# 12V-2A-buck.net
KiCad netlist of a schematic drawn in Altium Designer
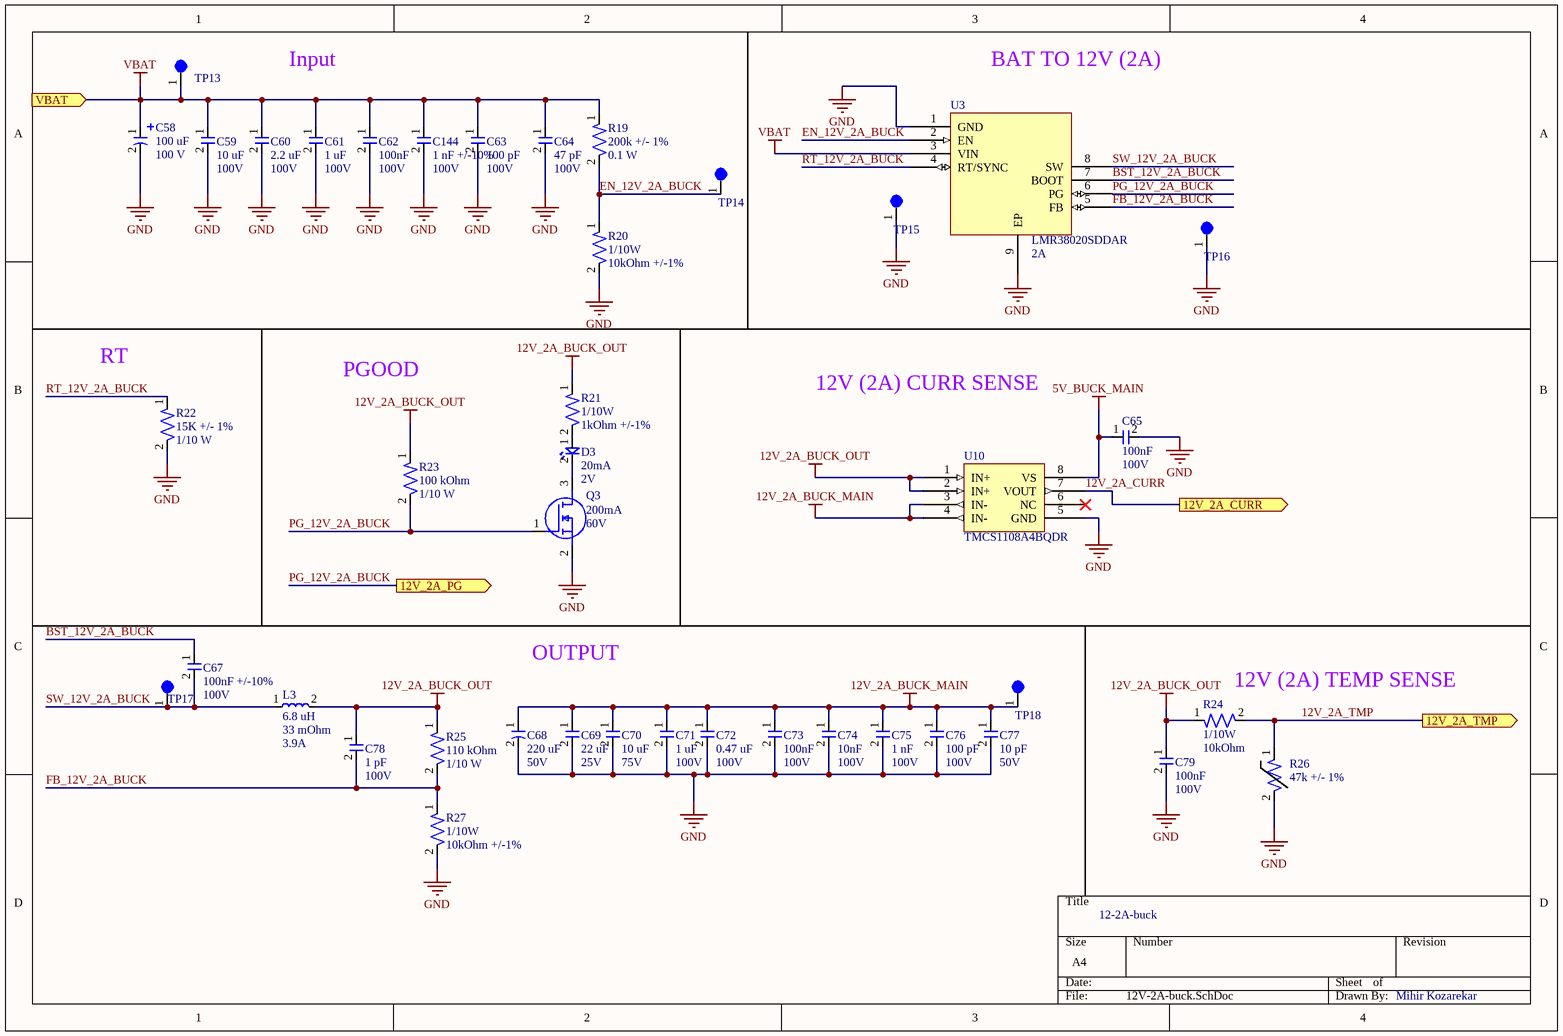
[diagram p0: 12V-2A-buck.SchDoc]

(export (version "E")
  (design (tool "Eeschema 10.0.6"))
  (components
    (comp (ref "C58")
      (value "100SEV100M12.5X16")
      (footprint "ELEC-100U-0001")
      (description "100 µF 100 V Aluminum Electrolytic Capacitors Radial, Can - SMD 2000 Hrs @ 85°C")
      (fields
        (field (name "MANUFACTURER") "Rubycon")
        (field (name "TOLERANCE") "+/- 20%")
        (field (name "CAPACITANCE") "100 uF")
        (field (name "VOLTAGE") "100 V")
      )
      (libsource (lib "MasterLib") (part "ELEC-100U-0001"))
    )
    (comp (ref "C59")
      (value "GRM32EC72A106KE05L")
      (footprint "CAP-1210")
      (description "10 µF ±10% 100V Ceramic Capacitor X7S 1210 (3225 Metric)")
      (fields (field (name "CAPCITANCE") "10 uF") (field (name "VOLTAGE RATING") "100V"))
      (libsource (lib "MasterLib") (part "CAP-10U-0003"))
    )
    (comp (ref "C60")
      (value "CL31B225KCHSNNE")
      (footprint "CAP-1206")
      (description "2.2 µF ±10% 100V Ceramic Capacitor X7R 1206 (3216 Metric)")
      (fields
        (field (name "MANUFACTURER") "Samsung Electro-Mechanics")
        (field (name "TOLERANCE") "+/- 10%")
        (field (name "CAPACITANCE") "2.2 uF")
        (field (name "VOLTAGE") "100V")
      )
      (libsource (lib "MasterLib") (part "CAP-2.2U-0003"))
    )
    (comp (ref "C61")
      (value "CL31B105KCHNNNE")
      (footprint "CAP-1206 - duplicate")
      (description "1 µF ±10% 100V Ceramic Capacitor X7R 1206 (3216 Metric)")
      (fields (field (name "CAPACITANCE") "1 uF") (field (name "VOLTAGE") "100V"))
      (libsource (lib "MasterLib") (part "CAP-1U-0001"))
    )
    (comp (ref "C62")
      (value "CC0603KRX7R0BB104")
      (footprint "CAP-0603")
      (description "CAP CER 0.1UF 100V X7R 0603")
      (fields
        (field (name "MANUFACTURER") "YAGEO")
        (field (name "CAPACITANCE") "100nF")
        (field (name "VOLTAGE RATING") "100V")
      )
      (libsource (lib "MasterLib") (part "CAP-100N-0001"))
    )
    (comp (ref "C63")
      (value "0603N101J101CT")
      (footprint "CAP-0603")
      (description "100 pF ±5% 100V Ceramic Capacitor C0G, NP0 0603 (1608 Metric)")
      (fields
        (field (name "TOLERANCE") "+/-5%")
        (field (name "CAPACITANCE") "100 pF")
        (field (name "VOLTAGE") "100V")
      )
      (libsource (lib "MasterLib") (part "CAP-100P-0002"))
    )
    (comp (ref "C64")
      (value "7447798111")
      (footprint "CAP-0603")
      (description "47 pF ±5% 100V Ceramic Capacitor C0G, NP0 0603 (1608 Metric)")
      (fields (field (name "CAPACITANCE") "47 pF") (field (name "VOLTAGE RATING") "100V"))
      (libsource (lib "MasterLib") (part "CAP-47P-0001"))
    )
    (comp (ref "C65")
      (value "CC0603KRX7R0BB104")
      (footprint "CAP-0603")
      (description "CAP CER 0.1UF 100V X7R 0603")
      (fields
        (field (name "MANUFACTURER") "YAGEO")
        (field (name "CAPACITANCE") "100nF")
        (field (name "VOLTAGE RATING") "100V")
      )
      (libsource (lib "MasterLib") (part "CAP-100N-0001"))
    )
    (comp (ref "C67")
      (value "CC0603KRX7R0BB104")
      (footprint "CAP-0603")
      (description "CAP CER 0.1UF 100V X7R 0603")
      (fields
        (field (name "MANUFACTURER") "YAGEO")
        (field (name "CAPACITANCE") "100nF +/-10%")
        (field (name "VOLTAGE RATING") "100V")
      )
      (libsource (lib "MasterLib") (part "CAP-100N-0001"))
    )
    (comp (ref "C68")
      (value "50TZV220M10X10.5")
      (footprint "ELEC-220U-0003")
      (description "220 µF 50 V Aluminum Electrolytic Capacitors Radial, Can - SMD 2000 Hrs @ 105°C")
      (fields (field (name "CAPACITANCE") "220 uF") (field (name "VOLTAGE RATING") "50V"))
      (libsource (lib "MasterLib") (part "ELEC-220U-0003"))
    )
    (comp (ref "C69")
      (value "CL32B226KAJNNNE")
      (footprint "CAP-1210")
      (description "22 µF ±10% 25V Ceramic Capacitor X7R 1210 (3225 Metric)")
      (fields
        (field (name "TOLERANCE") "+/- 10%")
        (field (name "CAPACITANCE") "22 uF")
        (field (name "VOLTAGE") "25V")
      )
      (libsource (lib "MasterLib") (part "CAP-22U-0003"))
    )
    (comp (ref "C70")
      (value "C3225X7R1N106K250AC")
      (footprint "CAP-1210")
      (description "10 µF ±10% 75V Ceramic Capacitor X7R 1210 (3225 Metric)")
      (fields (field (name "CAPACITANCE") "10 uF") (field (name "VOLTAGE RATING") "75V"))
      (libsource (lib "MasterLib") (part "CAP-10U-0004"))
    )
    (comp (ref "C71")
      (value "CL31B105KCHNNNE")
      (footprint "CAP-1206 - duplicate")
      (description "1 µF ±10% 100V Ceramic Capacitor X7R 1206 (3216 Metric)")
      (fields (field (name "CAPACITANCE") "1 uF") (field (name "VOLTAGE") "100V"))
      (libsource (lib "MasterLib") (part "CAP-1U-0001"))
    )
    (comp (ref "C72")
      (value "KAM21KR72A474KL")
      (footprint "CAP-0805")
      (description "0.47 µF ±10% 100V Ceramic Capacitor X7R 0805 (2012 Metric)")
      (fields
        (field (name "TOLERANCE") "+/- 10%")
        (field (name "CAPACITANCE") "0.47 uF")
        (field (name "VOLTAGE") "100V")
      )
      (libsource (lib "MasterLib") (part "CAP-0.47U-0001"))
    )
    (comp (ref "C73")
      (value "CC0603KRX7R0BB104")
      (footprint "CAP-0603")
      (description "CAP CER 0.1UF 100V X7R 0603")
      (fields
        (field (name "MANUFACTURER") "YAGEO")
        (field (name "CAPACITANCE") "100nF")
        (field (name "VOLTAGE RATING") "100V")
      )
      (libsource (lib "MasterLib") (part "CAP-100N-0001"))
    )
    (comp (ref "C74")
      (value "C1608C0G2A103J080AC")
      (footprint "CAP-0603")
      (description "CAP CER 10000PF 100V C0G 0603")
      (fields
        (field (name "MANUFACTURER") "TDK Corporation")
        (field (name "CAPACITANCE") "10nF")
        (field (name "VOLTAGE RATING") "100V")
      )
      (libsource (lib "MasterLib") (part "CAP-10N-0002"))
    )
    (comp (ref "C75")
      (value "C0603Y102K1RAC7867")
      (footprint "CAP-0603")
      (description "1000 pF ±10% 100V Ceramic Capacitor X7R 0603 (1608 Metric)")
      (fields (field (name "CAPACITANCE") "1 nF") (field (name "VOLTAGE") "100V"))
      (libsource (lib "MasterLib") (part "CAP-1N-0001"))
    )
    (comp (ref "C76")
      (value "0603N101J101CT")
      (footprint "CAP-0603")
      (description "100 pF ±5% 100V Ceramic Capacitor C0G, NP0 0603 (1608 Metric)")
      (fields
        (field (name "TOLERANCE") "+/-5%")
        (field (name "CAPACITANCE") "100 pF")
        (field (name "VOLTAGE") "100V")
      )
      (libsource (lib "MasterLib") (part "CAP-100P-0002"))
    )
    (comp (ref "C77")
      (value "0603N100J500CT")
      (footprint "CAP-0603")
      (description "10 pF ±5% 50V Ceramic Capacitor C0G, NP0 0603 (1608 Metric)")
      (fields
        (field (name "MANUFACTURER") "Walshin Technology Corporation")
        (field (name "CAPACITANCE") "10 pF")
        (field (name "VOLTAGE RATING") "50V")
      )
      (libsource (lib "MasterLib") (part "CAP-10P-0001"))
    )
    (comp (ref "C78")
      (value "885012006087")
      (footprint "CAP-0603")
      (description "1 pF ±0.25pF 100V Ceramic Capacitor C0G, NP0 0603 (1608 Metric)")
      (fields
        (field (name "TOLERANCE") "+/- 0.25 pF")
        (field (name "CAPACITANCE") "1 pF")
        (field (name "VOLTAGE") "100V")
      )
      (libsource (lib "MasterLib") (part "CAP-1P-0001"))
    )
    (comp (ref "C79")
      (value "CC0603KRX7R0BB104")
      (footprint "CAP-0603")
      (description "CAP CER 0.1UF 100V X7R 0603")
      (fields
        (field (name "MANUFACTURER") "YAGEO")
        (field (name "CAPACITANCE") "100nF")
        (field (name "VOLTAGE RATING") "100V")
      )
      (libsource (lib "MasterLib") (part "CAP-100N-0001"))
    )
    (comp (ref "C144")
      (value "C0603Y102K1RAC7867")
      (footprint "CAP-0603")
      (description "1000 pF ±10% 100V Ceramic Capacitor X7R 0603 (1608 Metric)")
      (fields (field (name "CAPACITANCE") "1 nF +/-10%") (field (name "VOLTAGE") "100V"))
      (libsource (lib "MasterLib") (part "CAP-1N-0001"))
    )
    (comp (ref "D3")
      (value "150060AS75000")
      (footprint "LED-0603")
      (description "CAP CER 0.1UF 100V X7R 0603")
      (fields
        (field (name "MANUFACTURER") "Wurth Electronik")
        (field (name "CURRENT RATING") "20mA")
        (field (name "VF") "2V")
      )
      (libsource (lib "MasterLib") (part "LED_Amber_0001"))
    )
    (comp (ref "L3")
      (value "SRN8040-6R8Y")
      (footprint "PWRIND-6.8U-0001")
      (description "6.8 µH Semi-Shielded Drum Core, Wirewound Inductor 3.9 A 33mOhm Max Nonstandard")
      (fields
        (field (name "TOLERANCE") "30%")
        (field (name "INDUCTANCE") "6.8 uH")
        (field (name "DCR") "33 mOhm")
        (field (name "DCI") "3.9A")
      )
      (libsource (lib "MasterLib") (part "PWRIND-6.8U-0001"))
    )
    (comp (ref "Q3")
      (value "T2N7002AK,LM")
      (footprint "NMOS-SOT23-3")
      (description "MOSFET N-CH 60V 200MA SOT23")
      (fields
        (field (name "MANUFACTURER") "Toshiba")
        (field (name "ID-CONTINUOUS") "200mA")
        (field (name "VDS-MAX") "60V")
      )
      (libsource (lib "MasterLib") (part "NMOS-200MA-0001"))
    )
    (comp (ref "R19")
      (value "ERJ-3EKF2003V")
      (footprint "RES-0603")
      (description "200 kOhms ±1% 0.1W, 1/10W Chip Resistor 0603 (1608 Metric) Automotive AEC-Q200 Thick Film")
      (fields
        (field (name "MANUFACTURER") "Panasonic Electronic Components")
        (field (name "RESISTANCE") "200k +/- 1%")
        (field (name "POWER RATING") "0.1 W")
      )
      (libsource (lib "MasterLib") (part "RES-200K-0001"))
    )
    (comp (ref "R20")
      (value "RC0603FR-0710KP")
      (footprint "RES-0603")
      (description "RES SMD 10K OHM 1% 1/10W 0603")
      (fields
        (field (name "MANUFACTURER") "YAGEO")
        (field (name "POWER RATING") "1/10W")
        (field (name "RESISTANCE") "10kOhm +/-1%")
      )
      (libsource (lib "MasterLib") (part "RES-10K-0002"))
    )
    (comp (ref "R21")
      (value "RT0603FRE131KL")
      (footprint "RES-0603")
      (description "1 kOhms ±1% 0.1W, 1/10W Chip Resistor 0603 (1608 Metric) Thin Film")
      (fields
        (field (name "MANUFACTURER") "YAGEO")
        (field (name "POWER RATING") "1/10W")
        (field (name "RESISTANCE") "1kOhm +/-1%")
      )
      (libsource (lib "MasterLib") (part "RES-1K-0002"))
    )
    (comp (ref "R22")
      (value "ERJ-2RKF1502X")
      (footprint "RES-0402")
      (description "15 kOhms ±1% 0.1W, 1/10W Chip Resistor 0402 (1005 Metric) Automotive AEC-Q200 Thick Film")
      (fields (field (name "RES") "15K +/- 1%") (field (name "POWER") "1/10 W"))
      (libsource (lib "MasterLib") (part "RES-15K-0001"))
    )
    (comp (ref "R23")
      (value "RC0603FR-07100KL")
      (footprint "RES-0603")
      (description "100 kOhms ±1% 0.1W, 1/10W Chip Resistor 0603 (1608 Metric) Moisture Resistant Thick Film")
      (fields
        (field (name "TOLERANCE") "+/- 1%")
        (field (name "RESISTANCE") "100 kOhm")
        (field (name "POWER") "1/10 W")
      )
      (libsource (lib "MasterLib") (part "RES-100K-0003"))
    )
    (comp (ref "R24")
      (value "RC0603FR-0710KP")
      (footprint "RES-0603")
      (description "RES SMD 10K OHM 1% 1/10W 0603")
      (fields
        (field (name "MANUFACTURER") "YAGEO")
        (field (name "POWER RATING") "1/10W")
        (field (name "RESISTANCE") "10kOhm")
      )
      (libsource (lib "MasterLib") (part "RES-10K-0002"))
    )
    (comp (ref "R25")
      (value "RC0603FR-07110KL")
      (footprint "RES-0603")
      (description "110 kOhms ±1% 0.1W, 1/10W Chip Resistor 0603 (1608 Metric) Moisture Resistant Thick Film")
      (fields
        (field (name "TOLERANCE") "+/- 1%")
        (field (name "RESISTANCE") "110 kOhm")
        (field (name "POWER") "1/10 W")
      )
      (libsource (lib "MasterLib") (part "RES-110K-0001"))
    )
    (comp (ref "R26")
      (value "TMP6431DECR")
      (footprint "RES-0402")
      (description "PTC Thermistor 47 kOhms 0402 (1006 Metric)")
      (fields (field (name "MANUFACTURER") "Texas Instruments") (field (name "RESISTANCE") "47k +/- 1%"))
      (libsource (lib "MasterLib") (part "THERM-47K-0001"))
    )
    (comp (ref "R27")
      (value "RC0603FR-0710KP")
      (footprint "RES-0603")
      (description "RES SMD 10K OHM 1% 1/10W 0603")
      (fields
        (field (name "MANUFACTURER") "YAGEO")
        (field (name "POWER RATING") "1/10W")
        (field (name "RESISTANCE") "10kOhm +/-1%")
      )
      (libsource (lib "MasterLib") (part "RES-10K-0002"))
    )
    (comp (ref "TP13")
      (value "5003")
      (footprint "TEST-POINT-0001")
      (description "Oranange PC Test Point, Miniature Phoisphor Bronze Silver Plating Through Hole Mounting Type")
      (libsource (lib "MasterLib") (part "TEST-POINT-0001"))
    )
    (comp (ref "TP14")
      (value "5003")
      (footprint "TEST-POINT-0001")
      (description "Oranange PC Test Point, Miniature Phoisphor Bronze Silver Plating Through Hole Mounting Type")
      (libsource (lib "MasterLib") (part "TEST-POINT-0001"))
    )
    (comp (ref "TP15")
      (value "5003")
      (footprint "TEST-POINT-0001")
      (description "Oranange PC Test Point, Miniature Phoisphor Bronze Silver Plating Through Hole Mounting Type")
      (libsource (lib "MasterLib") (part "TEST-POINT-0001"))
    )
    (comp (ref "TP16")
      (value "5003")
      (footprint "TEST-POINT-0001")
      (description "Oranange PC Test Point, Miniature Phoisphor Bronze Silver Plating Through Hole Mounting Type")
      (libsource (lib "MasterLib") (part "TEST-POINT-0001"))
    )
    (comp (ref "TP17")
      (value "5003")
      (footprint "TEST-POINT-0001")
      (description "Oranange PC Test Point, Miniature Phoisphor Bronze Silver Plating Through Hole Mounting Type")
      (libsource (lib "MasterLib") (part "TEST-POINT-0001"))
    )
    (comp (ref "TP18")
      (value "5003")
      (footprint "TEST-POINT-0001")
      (description "Oranange PC Test Point, Miniature Phoisphor Bronze Silver Plating Through Hole Mounting Type")
      (libsource (lib "MasterLib") (part "TEST-POINT-0001"))
    )
    (comp (ref "U3")
      (value "LMR38020SDDAR")
      (footprint "IC-8PowerSOIC")
      (description "Buck Switching Regulator IC Positive Adjustable 1V 1 Output 2A 8-PowerSOIC (0.154\", 3.90mm Width)")
      (fields (field (name "CURRENT") "2A"))
      (libsource (lib "MasterLib") (part "IC-BUCK-0007"))
    )
    (comp (ref "U10")
      (value "TMCS1108A4BQDR")
      (footprint "IC-CURRENT-0001")
      (description "Current Sensor 1 Channel Hall Effect Bidirectional 8-SOIC (0.154\", 3.90mm Width)")
      (libsource (lib "MasterLib") (part "IC-CURRENT-0004"))
    )
  )
  (nets
    (net (code "1") (name "/12V_2A_CURR") (class "Default")
      (node (ref "U10") (pin "7") (pinfunction "VOUT_7") (pintype "output"))
    )
    (net (code "2") (name "/12V_2A_TMP") (class "Default")
      (node (ref "R24") (pin "2") (pinfunction "2_2") (pintype "passive"))
      (node (ref "R26") (pin "1") (pinfunction "1_1") (pintype "passive"))
    )
    (net (code "3") (name "/BST_12V_2A_BUCK") (class "Default")
      (node (ref "C67") (pin "1") (pinfunction "1_1") (pintype "passive"))
      (node (ref "U3") (pin "7") (pinfunction "BOOT_7") (pintype "power_in"))
    )
    (net (code "4") (name "/EN_12V_2A_BUCK") (class "Default")
      (node (ref "R19") (pin "2") (pinfunction "2_2") (pintype "passive"))
      (node (ref "R20") (pin "1") (pinfunction "1_1") (pintype "passive"))
      (node (ref "TP14") (pin "1") (pinfunction "0_1") (pintype "passive"))
      (node (ref "U3") (pin "2") (pinfunction "EN_2") (pintype "input"))
    )
    (net (code "5") (name "/FB_12V_2A_BUCK") (class "Default")
      (node (ref "C78") (pin "2") (pinfunction "2_2") (pintype "passive"))
      (node (ref "R25") (pin "2") (pinfunction "2_2") (pintype "passive"))
      (node (ref "R27") (pin "1") (pinfunction "1_1") (pintype "passive"))
      (node (ref "U3") (pin "5") (pinfunction "FB_5") (pintype "bidirectional"))
    )
    (net (code "6") (name "/PG_12V_2A_BUCK") (class "Default")
      (node (ref "Q3") (pin "1") (pinfunction "G_1") (pintype "passive"))
      (node (ref "R23") (pin "2") (pinfunction "2_2") (pintype "passive"))
      (node (ref "U3") (pin "6") (pinfunction "PG_6") (pintype "bidirectional"))
    )
    (net (code "7") (name "/RT_12V_2A_BUCK") (class "Default")
      (node (ref "R22") (pin "1") (pinfunction "1_1") (pintype "passive"))
      (node (ref "U3") (pin "4") (pinfunction "RT/SYNC_4") (pintype "bidirectional"))
    )
    (net (code "8") (name "/SW_12V_2A_BUCK") (class "Default")
      (node (ref "C67") (pin "2") (pinfunction "2_2") (pintype "passive"))
      (node (ref "L3") (pin "1") (pinfunction "1_1") (pintype "passive"))
      (node (ref "TP17") (pin "1") (pinfunction "0_1") (pintype "passive"))
      (node (ref "U3") (pin "8") (pinfunction "SW_8") (pintype "power_in"))
    )
    (net (code "9") (name "5V_BUCK_MAIN") (class "Default")
      (node (ref "C65") (pin "1") (pinfunction "1_1") (pintype "passive"))
      (node (ref "U10") (pin "8") (pinfunction "VS_8") (pintype "power_in"))
    )
    (net (code "10") (name "12V_2A_BUCK_MAIN") (class "Default")
      (node (ref "C68") (pin "1") (pinfunction "1_1") (pintype "passive"))
      (node (ref "C69") (pin "1") (pinfunction "1_1") (pintype "passive"))
      (node (ref "C70") (pin "1") (pinfunction "1_1") (pintype "passive"))
      (node (ref "C71") (pin "1") (pinfunction "1_1") (pintype "passive"))
      (node (ref "C72") (pin "1") (pinfunction "1_1") (pintype "passive"))
      (node (ref "C73") (pin "1") (pinfunction "1_1") (pintype "passive"))
      (node (ref "C74") (pin "1") (pinfunction "1_1") (pintype "passive"))
      (node (ref "C75") (pin "1") (pinfunction "1_1") (pintype "passive"))
      (node (ref "C76") (pin "1") (pinfunction "1_1") (pintype "passive"))
      (node (ref "C77") (pin "1") (pinfunction "1_1") (pintype "passive"))
      (node (ref "TP18") (pin "1") (pinfunction "0_1") (pintype "passive"))
      (node (ref "U10") (pin "3") (pinfunction "IN-_3") (pintype "output"))
      (node (ref "U10") (pin "4") (pinfunction "IN-_4") (pintype "output"))
    )
    (net (code "11") (name "12V_2A_BUCK_OUT") (class "Default")
      (node (ref "C78") (pin "1") (pinfunction "1_1") (pintype "passive"))
      (node (ref "C79") (pin "1") (pinfunction "1_1") (pintype "passive"))
      (node (ref "L3") (pin "2") (pinfunction "2_2") (pintype "passive"))
      (node (ref "R21") (pin "1") (pinfunction "1_1") (pintype "passive"))
      (node (ref "R23") (pin "1") (pinfunction "1_1") (pintype "passive"))
      (node (ref "R24") (pin "1") (pinfunction "1_1") (pintype "passive"))
      (node (ref "R25") (pin "1") (pinfunction "1_1") (pintype "passive"))
      (node (ref "U10") (pin "1") (pinfunction "IN+_1") (pintype "input"))
      (node (ref "U10") (pin "2") (pinfunction "IN+_2") (pintype "input"))
    )
    (net (code "12") (name "GND") (class "Default")
      (node (ref "C144") (pin "2") (pinfunction "2_2") (pintype "passive"))
      (node (ref "C58") (pin "2") (pinfunction "2_2") (pintype "passive"))
      (node (ref "C59") (pin "2") (pinfunction "2_2") (pintype "passive"))
      (node (ref "C60") (pin "2") (pinfunction "2_2") (pintype "passive"))
      (node (ref "C61") (pin "2") (pinfunction "2_2") (pintype "passive"))
      (node (ref "C62") (pin "2") (pinfunction "2_2") (pintype "passive"))
      (node (ref "C63") (pin "2") (pinfunction "2_2") (pintype "passive"))
      (node (ref "C64") (pin "2") (pinfunction "2_2") (pintype "passive"))
      (node (ref "C65") (pin "2") (pinfunction "2_2") (pintype "passive"))
      (node (ref "C68") (pin "2") (pinfunction "2_2") (pintype "passive"))
      (node (ref "C69") (pin "2") (pinfunction "2_2") (pintype "passive"))
      (node (ref "C70") (pin "2") (pinfunction "2_2") (pintype "passive"))
      (node (ref "C71") (pin "2") (pinfunction "2_2") (pintype "passive"))
      (node (ref "C72") (pin "2") (pinfunction "2_2") (pintype "passive"))
      (node (ref "C73") (pin "2") (pinfunction "2_2") (pintype "passive"))
      (node (ref "C74") (pin "2") (pinfunction "2_2") (pintype "passive"))
      (node (ref "C75") (pin "2") (pinfunction "2_2") (pintype "passive"))
      (node (ref "C76") (pin "2") (pinfunction "2_2") (pintype "passive"))
      (node (ref "C77") (pin "2") (pinfunction "2_2") (pintype "passive"))
      (node (ref "C79") (pin "2") (pinfunction "2_2") (pintype "passive"))
      (node (ref "Q3") (pin "2") (pinfunction "S_2") (pintype "passive"))
      (node (ref "R20") (pin "2") (pinfunction "2_2") (pintype "passive"))
      (node (ref "R22") (pin "2") (pinfunction "2_2") (pintype "passive"))
      (node (ref "R26") (pin "2") (pinfunction "2_2") (pintype "passive"))
      (node (ref "R27") (pin "2") (pinfunction "2_2") (pintype "passive"))
      (node (ref "TP15") (pin "1") (pinfunction "0_1") (pintype "passive"))
      (node (ref "TP16") (pin "1") (pinfunction "0_1") (pintype "passive"))
      (node (ref "U10") (pin "5") (pinfunction "GND_5") (pintype "power_in"))
      (node (ref "U3") (pin "1") (pinfunction "GND_1") (pintype "power_in"))
      (node (ref "U3") (pin "9") (pinfunction "EP_9") (pintype "power_in"))
    )
    (net (code "13") (name "Net-(D3-Pad1)") (class "Default")
      (node (ref "D3") (pin "1") (pinfunction "1_1") (pintype "passive"))
      (node (ref "R21") (pin "2") (pinfunction "2_2") (pintype "passive"))
    )
    (net (code "14") (name "Net-(Q3-D)") (class "Default")
      (node (ref "D3") (pin "2") (pinfunction "2_2") (pintype "passive"))
      (node (ref "Q3") (pin "3") (pinfunction "D_3") (pintype "passive"))
    )
    (net (code "15") (name "VBAT") (class "Default")
      (node (ref "C144") (pin "1") (pinfunction "1_1") (pintype "passive"))
      (node (ref "C58") (pin "1") (pinfunction "1_1") (pintype "passive"))
      (node (ref "C59") (pin "1") (pinfunction "1_1") (pintype "passive"))
      (node (ref "C60") (pin "1") (pinfunction "1_1") (pintype "passive"))
      (node (ref "C61") (pin "1") (pinfunction "1_1") (pintype "passive"))
      (node (ref "C62") (pin "1") (pinfunction "1_1") (pintype "passive"))
      (node (ref "C63") (pin "1") (pinfunction "1_1") (pintype "passive"))
      (node (ref "C64") (pin "1") (pinfunction "1_1") (pintype "passive"))
      (node (ref "R19") (pin "1") (pinfunction "1_1") (pintype "passive"))
      (node (ref "TP13") (pin "1") (pinfunction "0_1") (pintype "passive"))
      (node (ref "U3") (pin "3") (pinfunction "VIN_3") (pintype "power_in"))
    )
    (net (code "16") (name "unconnected-(U10-NC-Pad6)") (class "Default")
      (node (ref "U10") (pin "6") (pinfunction "NC_6") (pintype "tri_state+no_connect"))
    )
  )
)
